# DressCode.net
KiCad netlist of a schematic drawn in EAGLE
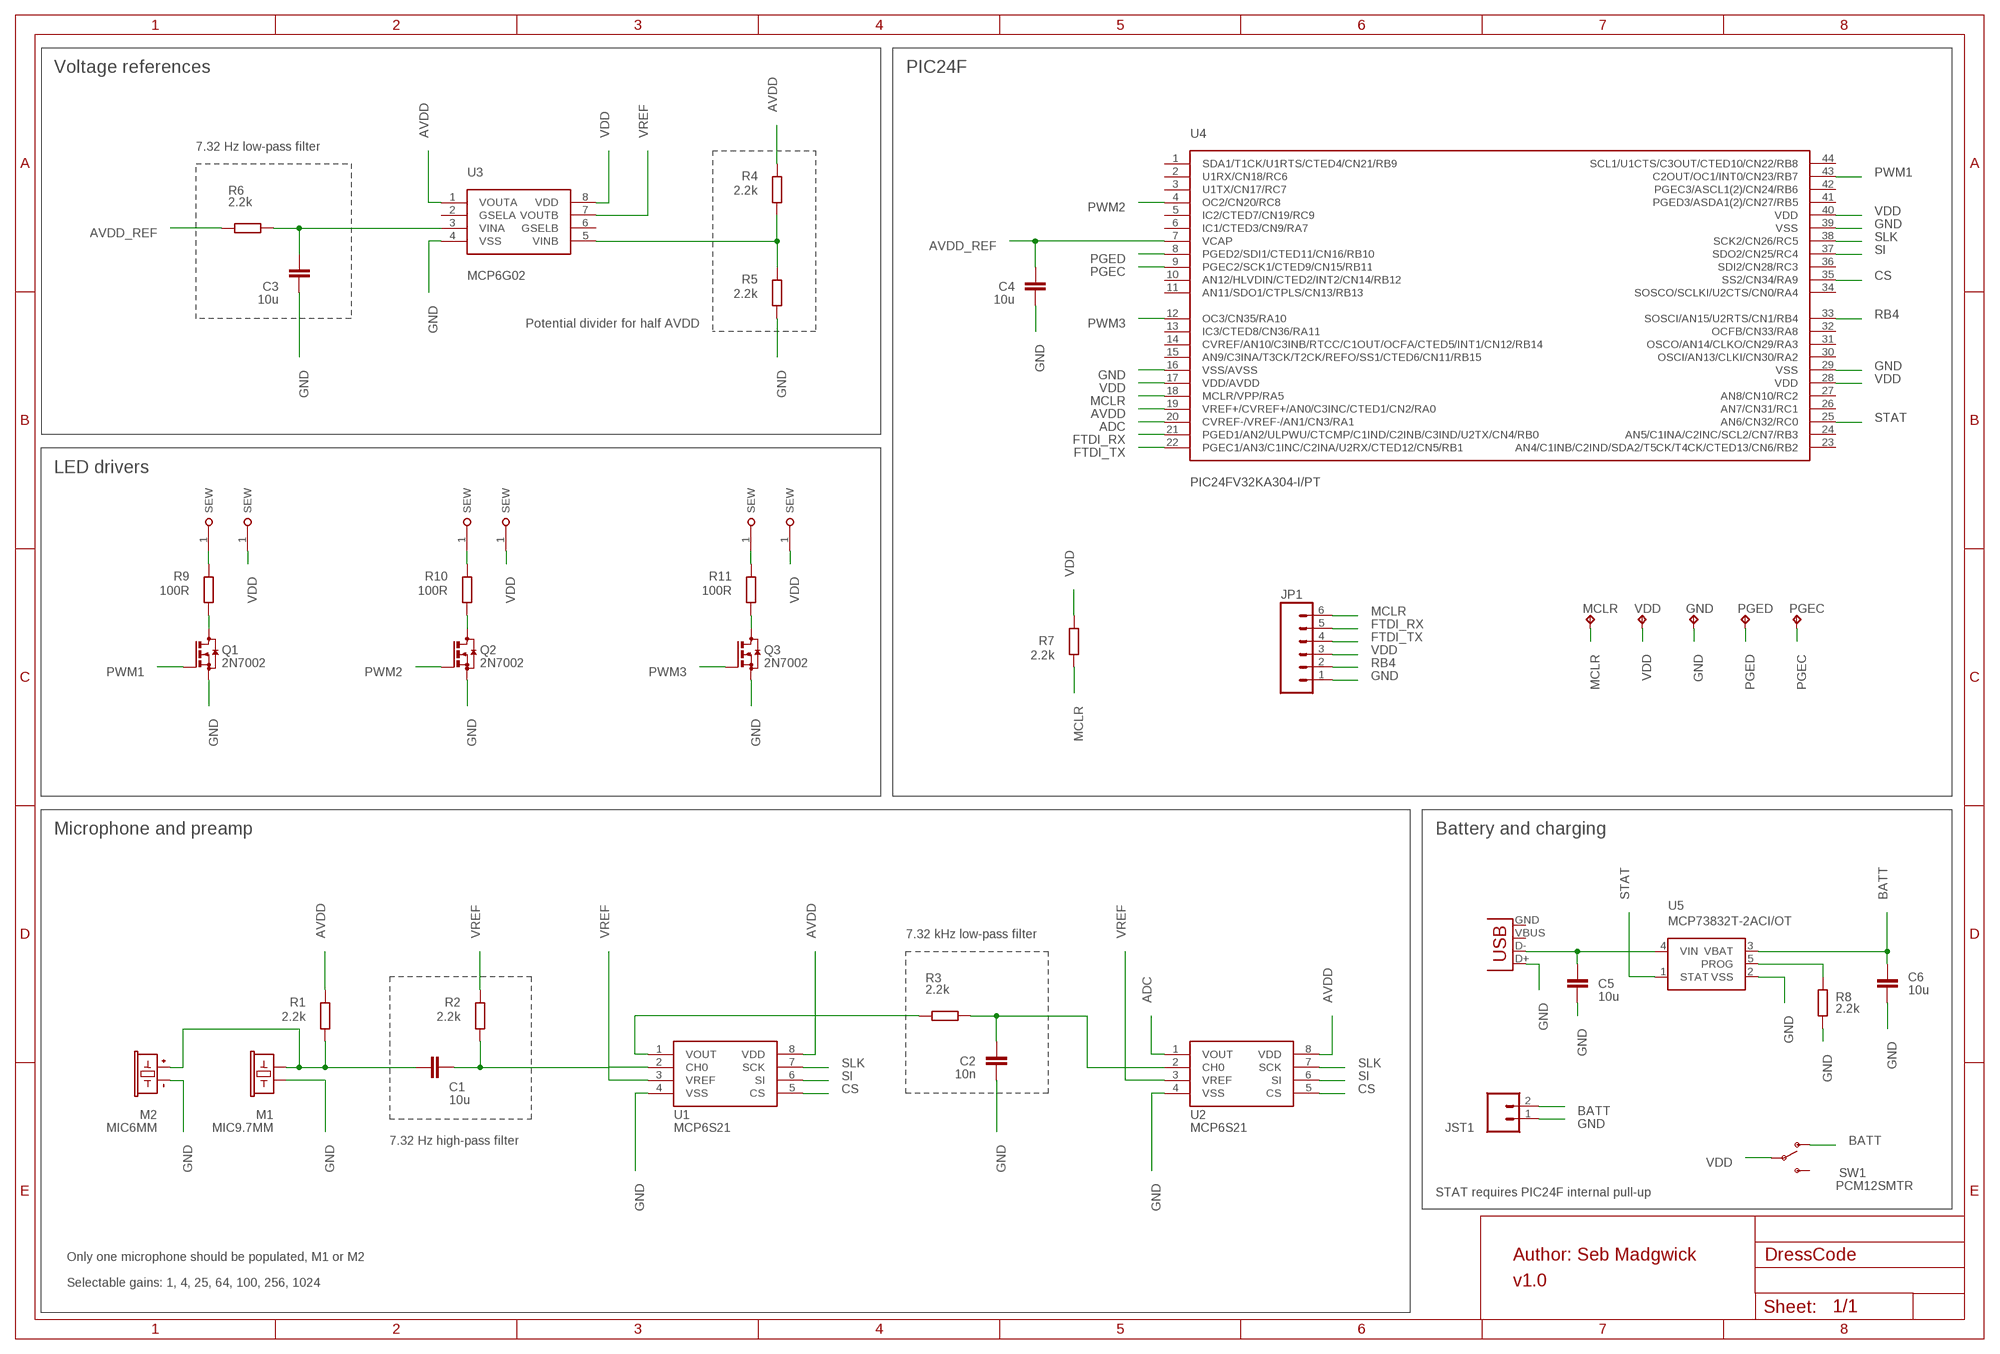
[diagram p0: schematic, sheet 1]

(export (version "E")
  (design (tool "Eeschema 10.0.6"))
  (components
    (comp (ref "C1")
      (value "10u")
      (footprint "eagle-import:C0805")
      (libsource (lib "eagle-import") (part "C-EUC0805"))
    )
    (comp (ref "C2")
      (value "10n")
      (footprint "eagle-import:C0805")
      (libsource (lib "eagle-import") (part "C-EUC0805"))
    )
    (comp (ref "C3")
      (value "10u")
      (footprint "eagle-import:C0805")
      (libsource (lib "eagle-import") (part "C-EUC0805"))
    )
    (comp (ref "C4")
      (value "10u")
      (footprint "eagle-import:C0805")
      (libsource (lib "eagle-import") (part "C-EUC0805"))
    )
    (comp (ref "C5")
      (value "10u")
      (footprint "eagle-import:C0805")
      (libsource (lib "eagle-import") (part "C-EUC0805"))
    )
    (comp (ref "C6")
      (value "10u")
      (footprint "eagle-import:C0805")
      (libsource (lib "eagle-import") (part "C-EUC0805"))
    )
    (comp (ref "GND")
      (value "TPTP16R")
      (footprint "eagle-import:TP16R")
      (libsource (lib "eagle-import") (part "TPTP16R"))
    )
    (comp (ref "JP1")
      (value "M06SIP")
      (footprint "eagle-import:1X06")
      (libsource (lib "eagle-import") (part "M06SIP"))
    )
    (comp (ref "JST1")
      (value "M02-JST-2MM-SMT")
      (footprint "eagle-import:JST-2-SMD")
      (libsource (lib "eagle-import") (part "M02-JST-2MM-SMT"))
    )
    (comp (ref "M1")
      (value "MIC9.7MM")
      (footprint "eagle-import:MIC-9.7MM")
      (libsource (lib "eagle-import") (part "MIC9.7MM"))
    )
    (comp (ref "M2")
      (value "MIC6MM")
      (footprint "eagle-import:MIC-SMD")
      (libsource (lib "eagle-import") (part "MIC6MM"))
    )
    (comp (ref "MCLR")
      (value "TPTP16R")
      (footprint "eagle-import:TP16R")
      (libsource (lib "eagle-import") (part "TPTP16R"))
    )
    (comp (ref "PGEC")
      (value "TPTP16R")
      (footprint "eagle-import:TP16R")
      (libsource (lib "eagle-import") (part "TPTP16R"))
    )
    (comp (ref "PGED")
      (value "TPTP16R")
      (footprint "eagle-import:TP16R")
      (libsource (lib "eagle-import") (part "TPTP16R"))
    )
    (comp (ref "Q1")
      (value "2N7002")
      (footprint "eagle-import:SOT23")
      (libsource (lib "eagle-import") (part "BSS123"))
    )
    (comp (ref "Q2")
      (value "2N7002")
      (footprint "eagle-import:SOT23")
      (libsource (lib "eagle-import") (part "BSS123"))
    )
    (comp (ref "Q3")
      (value "2N7002")
      (footprint "eagle-import:SOT23")
      (libsource (lib "eagle-import") (part "BSS123"))
    )
    (comp (ref "R1")
      (value "2.2k")
      (footprint "eagle-import:R0805")
      (libsource (lib "eagle-import") (part "R-EU_R0805"))
    )
    (comp (ref "R2")
      (value "2.2k")
      (footprint "eagle-import:R0805")
      (libsource (lib "eagle-import") (part "R-EU_R0805"))
    )
    (comp (ref "R3")
      (value "2.2k")
      (footprint "eagle-import:R0805")
      (libsource (lib "eagle-import") (part "R-EU_R0805"))
    )
    (comp (ref "R4")
      (value "2.2k")
      (footprint "eagle-import:R0805")
      (libsource (lib "eagle-import") (part "R-EU_R0805"))
    )
    (comp (ref "R5")
      (value "2.2k")
      (footprint "eagle-import:R0805")
      (libsource (lib "eagle-import") (part "R-EU_R0805"))
    )
    (comp (ref "R6")
      (value "2.2k")
      (footprint "eagle-import:R0805")
      (libsource (lib "eagle-import") (part "R-EU_R0805"))
    )
    (comp (ref "R7")
      (value "2.2k")
      (footprint "eagle-import:R0805")
      (libsource (lib "eagle-import") (part "R-EU_R0805"))
    )
    (comp (ref "R8")
      (value "2.2k")
      (footprint "eagle-import:R0805")
      (libsource (lib "eagle-import") (part "R-EU_R0805"))
    )
    (comp (ref "R9")
      (value "100R")
      (footprint "eagle-import:R0805")
      (libsource (lib "eagle-import") (part "R-EU_R0805"))
    )
    (comp (ref "R10")
      (value "100R")
      (footprint "eagle-import:R0805")
      (libsource (lib "eagle-import") (part "R-EU_R0805"))
    )
    (comp (ref "R11")
      (value "100R")
      (footprint "eagle-import:R0805")
      (libsource (lib "eagle-import") (part "R-EU_R0805"))
    )
    (comp (ref "SW1")
      (value "PCM12SMTR")
      (footprint "eagle-import:PCM12SMTR")
      (libsource (lib "eagle-import") (part "PCM12SMTR"))
    )
    (comp (ref "U$4")
      (value "DRESSCODE_SEW_PADC")
      (footprint "eagle-import:DRESSCODE_SEW_PAD_CIRC")
      (libsource (lib "eagle-import") (part "DRESSCODE_SEW_PADC"))
    )
    (comp (ref "U$5")
      (value "DRESSCODE_SEW_PADC")
      (footprint "eagle-import:DRESSCODE_SEW_PAD_CIRC")
      (libsource (lib "eagle-import") (part "DRESSCODE_SEW_PADC"))
    )
    (comp (ref "U$6")
      (value "DRESSCODE_SEW_PADC")
      (footprint "eagle-import:DRESSCODE_SEW_PAD_CIRC")
      (libsource (lib "eagle-import") (part "DRESSCODE_SEW_PADC"))
    )
    (comp (ref "U$7")
      (value "DRESSCODE_SEW_PADS")
      (footprint "eagle-import:DRESSCODE_SEW_PAD_SQR")
      (libsource (lib "eagle-import") (part "DRESSCODE_SEW_PADS"))
    )
    (comp (ref "U$8")
      (value "DRESSCODE_SEW_PADS")
      (footprint "eagle-import:DRESSCODE_SEW_PAD_SQR")
      (libsource (lib "eagle-import") (part "DRESSCODE_SEW_PADS"))
    )
    (comp (ref "U$10")
      (value "DRESSCODE_SEW_PADS")
      (footprint "eagle-import:DRESSCODE_SEW_PAD_SQR")
      (libsource (lib "eagle-import") (part "DRESSCODE_SEW_PADS"))
    )
    (comp (ref "U1")
      (value "MCP6S21")
      (footprint "eagle-import:SOIC-8")
      (libsource (lib "eagle-import") (part "MCP6S21"))
    )
    (comp (ref "U2")
      (value "MCP6S21")
      (footprint "eagle-import:SOIC-8")
      (libsource (lib "eagle-import") (part "MCP6S21"))
    )
    (comp (ref "U3")
      (value "MCP6G02")
      (footprint "eagle-import:SOIC-8")
      (libsource (lib "eagle-import") (part "MCP6G02"))
    )
    (comp (ref "U4")
      (value "PIC24FV32KA304-I/PT")
      (footprint "eagle-import:TQFP44")
      (libsource (lib "eagle-import") (part "PIC24FV32KA304-I/PT"))
    )
    (comp (ref "U5")
      (value "MCP73832T-2ACI/OT")
      (footprint "eagle-import:SOT23-5")
      (libsource (lib "eagle-import") (part "MCP73831"))
    )
    (comp (ref "USB1")
      (value "USB-MICROB")
      (footprint "eagle-import:USB-MICROB")
      (libsource (lib "eagle-import") (part "USB-MICROB"))
    )
    (comp (ref "VDD")
      (value "TPTP16R")
      (footprint "eagle-import:TP16R")
      (libsource (lib "eagle-import") (part "TPTP16R"))
    )
  )
  (nets
    (net (code "1") (name "/ADC") (class "Default")
      (node (ref "U2") (pin "1") (pinfunction "VOUT_1") (pintype "bidirectional"))
      (node (ref "U4") (pin "20") (pinfunction "CVREF-/VREF-/AN1/CN3/RA1_20") (pintype "bidirectional"))
    )
    (net (code "2") (name "/AVDD") (class "Default")
      (node (ref "R1") (pin "2") (pinfunction "2_2") (pintype "passive"))
      (node (ref "R4") (pin "2") (pinfunction "2_2") (pintype "passive"))
      (node (ref "U1") (pin "8") (pinfunction "VDD_8") (pintype "bidirectional"))
      (node (ref "U2") (pin "8") (pinfunction "VDD_8") (pintype "bidirectional"))
      (node (ref "U3") (pin "1") (pinfunction "VOUTA_1") (pintype "bidirectional"))
      (node (ref "U4") (pin "19") (pinfunction "VREF+/CVREF+/AN0/C3INC/CTED1/CN2/RA0_19") (pintype "bidirectional"))
    )
    (net (code "3") (name "/AVDD_REF") (class "Default")
      (node (ref "C4") (pin "2") (pinfunction "2_2") (pintype "passive"))
      (node (ref "R6") (pin "1") (pinfunction "1_1") (pintype "passive"))
      (node (ref "U4") (pin "7") (pinfunction "VCAP_7") (pintype "bidirectional"))
    )
    (net (code "4") (name "/BATT") (class "Default")
      (node (ref "C6") (pin "2") (pinfunction "2_2") (pintype "passive"))
      (node (ref "JST1") (pin "2") (pinfunction "2_2") (pintype "passive"))
      (node (ref "SW1") (pin "1") (pinfunction "O_1") (pintype "passive"))
      (node (ref "U5") (pin "3") (pinfunction "VBAT_3") (pintype "power_in"))
    )
    (net (code "5") (name "/CS") (class "Default")
      (node (ref "U1") (pin "5") (pinfunction "CS_5") (pintype "bidirectional"))
      (node (ref "U2") (pin "5") (pinfunction "CS_5") (pintype "bidirectional"))
      (node (ref "U4") (pin "35") (pinfunction "SS2/CN34/RA9_35") (pintype "bidirectional"))
    )
    (net (code "6") (name "/FTDI_RX") (class "Default")
      (node (ref "JP1") (pin "5") (pinfunction "5_5") (pintype "passive"))
      (node (ref "U4") (pin "21") (pinfunction "PGED1/AN2/ULPWU/CTCMP/C1IND/C2INB/C3IND/U2TX/CN4/RB0_21") (pintype "bidirectional"))
    )
    (net (code "7") (name "/FTDI_TX") (class "Default")
      (node (ref "JP1") (pin "4") (pinfunction "4_4") (pintype "passive"))
      (node (ref "U4") (pin "22") (pinfunction "PGEC1/AN3/C1INC/C2INA/U2RX/CTED12/CN5/RB1_22") (pintype "bidirectional"))
    )
    (net (code "8") (name "/GND") (class "Default")
      (node (ref "C2") (pin "2") (pinfunction "2_2") (pintype "passive"))
      (node (ref "C3") (pin "1") (pinfunction "1_1") (pintype "passive"))
      (node (ref "C4") (pin "1") (pinfunction "1_1") (pintype "passive"))
      (node (ref "C5") (pin "1") (pinfunction "1_1") (pintype "passive"))
      (node (ref "C6") (pin "1") (pinfunction "1_1") (pintype "passive"))
      (node (ref "GND") (pin "TP") (pinfunction "TP_TP") (pintype "input"))
      (node (ref "JP1") (pin "1") (pinfunction "1_1") (pintype "passive"))
      (node (ref "JST1") (pin "1") (pinfunction "1_1") (pintype "passive"))
      (node (ref "M1") (pin "2") (pinfunction "2_2") (pintype "passive"))
      (node (ref "M2") (pin "-") (pinfunction "-_-") (pintype "passive"))
      (node (ref "Q1") (pin "2") (pinfunction "S_2") (pintype "passive"))
      (node (ref "Q2") (pin "2") (pinfunction "S_2") (pintype "passive"))
      (node (ref "Q3") (pin "2") (pinfunction "S_2") (pintype "passive"))
      (node (ref "R5") (pin "1") (pinfunction "1_1") (pintype "passive"))
      (node (ref "R8") (pin "1") (pinfunction "1_1") (pintype "passive"))
      (node (ref "U1") (pin "4") (pinfunction "VSS_4") (pintype "bidirectional"))
      (node (ref "U2") (pin "4") (pinfunction "VSS_4") (pintype "bidirectional"))
      (node (ref "U3") (pin "4") (pinfunction "VSS_4") (pintype "bidirectional"))
      (node (ref "U4") (pin "16") (pinfunction "VSS/AVSS_16") (pintype "bidirectional"))
      (node (ref "U4") (pin "29") (pinfunction "VSS_29") (pintype "bidirectional"))
      (node (ref "U4") (pin "39") (pinfunction "VSS_39") (pintype "bidirectional"))
      (node (ref "U5") (pin "2") (pinfunction "VSS_2") (pintype "power_in"))
      (node (ref "USB1") (pin "D+") (pinfunction "D+_D+") (pintype "bidirectional"))
    )
    (net (code "9") (name "/MCLR") (class "Default")
      (node (ref "JP1") (pin "6") (pinfunction "6_6") (pintype "passive"))
      (node (ref "MCLR") (pin "TP") (pinfunction "TP_TP") (pintype "input"))
      (node (ref "R7") (pin "1") (pinfunction "1_1") (pintype "passive"))
      (node (ref "U4") (pin "18") (pinfunction "MCLR/VPP/RA5_18") (pintype "bidirectional"))
    )
    (net (code "10") (name "/PGEC") (class "Default")
      (node (ref "PGEC") (pin "TP") (pinfunction "TP_TP") (pintype "input"))
      (node (ref "U4") (pin "9") (pinfunction "PGEC2/SCK1/CTED9/CN15/RB11_9") (pintype "bidirectional"))
    )
    (net (code "11") (name "/PGED") (class "Default")
      (node (ref "PGED") (pin "TP") (pinfunction "TP_TP") (pintype "input"))
      (node (ref "U4") (pin "8") (pinfunction "PGED2/SDI1/CTED11/CN16/RB10_8") (pintype "bidirectional"))
    )
    (net (code "12") (name "/PWM1") (class "Default")
      (node (ref "Q1") (pin "1") (pinfunction "G_1") (pintype "passive"))
      (node (ref "U4") (pin "43") (pinfunction "C2OUT/OC1/INT0/CN23/RB7_43") (pintype "bidirectional"))
    )
    (net (code "13") (name "/PWM2") (class "Default")
      (node (ref "Q2") (pin "1") (pinfunction "G_1") (pintype "passive"))
      (node (ref "U4") (pin "4") (pinfunction "OC2/CN20/RC8_4") (pintype "bidirectional"))
    )
    (net (code "14") (name "/PWM3") (class "Default")
      (node (ref "Q3") (pin "1") (pinfunction "G_1") (pintype "passive"))
      (node (ref "U4") (pin "12") (pinfunction "OC3/CN35/RA10_12") (pintype "bidirectional"))
    )
    (net (code "15") (name "/RB4") (class "Default")
      (node (ref "JP1") (pin "2") (pinfunction "2_2") (pintype "passive"))
      (node (ref "U4") (pin "33") (pinfunction "SOSCI/AN15/U2RTS/CN1/RB4_33") (pintype "bidirectional"))
    )
    (net (code "16") (name "/SI") (class "Default")
      (node (ref "U1") (pin "6") (pinfunction "SI_6") (pintype "bidirectional"))
      (node (ref "U2") (pin "6") (pinfunction "SI_6") (pintype "bidirectional"))
      (node (ref "U4") (pin "37") (pinfunction "SDO2/CN25/RC4_37") (pintype "bidirectional"))
    )
    (net (code "17") (name "/SLK") (class "Default")
      (node (ref "U1") (pin "7") (pinfunction "SCK_7") (pintype "bidirectional"))
      (node (ref "U2") (pin "7") (pinfunction "SCK_7") (pintype "bidirectional"))
      (node (ref "U4") (pin "38") (pinfunction "SCK2/CN26/RC5_38") (pintype "bidirectional"))
    )
    (net (code "18") (name "/STAT") (class "Default")
      (node (ref "U4") (pin "25") (pinfunction "AN6/CN32/RC0_25") (pintype "bidirectional"))
      (node (ref "U5") (pin "1") (pinfunction "STAT_1") (pintype "output"))
    )
    (net (code "19") (name "/VDD") (class "Default")
      (node (ref "JP1") (pin "3") (pinfunction "3_3") (pintype "passive"))
      (node (ref "R7") (pin "2") (pinfunction "2_2") (pintype "passive"))
      (node (ref "SW1") (pin "2") (pinfunction "P_2") (pintype "passive"))
      (node (ref "U$4") (pin "1") (pinfunction "SEW_1") (pintype "bidirectional"))
      (node (ref "U$5") (pin "1") (pinfunction "SEW_1") (pintype "bidirectional"))
      (node (ref "U$6") (pin "1") (pinfunction "SEW_1") (pintype "bidirectional"))
      (node (ref "U3") (pin "8") (pinfunction "VDD_8") (pintype "bidirectional"))
      (node (ref "U4") (pin "17") (pinfunction "VDD/AVDD_17") (pintype "bidirectional"))
      (node (ref "U4") (pin "28") (pinfunction "VDD_28") (pintype "bidirectional"))
      (node (ref "U4") (pin "40") (pinfunction "VDD_40") (pintype "bidirectional"))
      (node (ref "VDD") (pin "TP") (pinfunction "TP_TP") (pintype "input"))
    )
    (net (code "20") (name "/VREF") (class "Default")
      (node (ref "R2") (pin "2") (pinfunction "2_2") (pintype "passive"))
      (node (ref "U1") (pin "3") (pinfunction "VREF_3") (pintype "bidirectional"))
      (node (ref "U2") (pin "3") (pinfunction "VREF_3") (pintype "bidirectional"))
      (node (ref "U3") (pin "7") (pinfunction "VOUTB_7") (pintype "bidirectional"))
    )
    (net (code "21") (name "Net-(C1-Pad1)") (class "Default")
      (node (ref "C1") (pin "1") (pinfunction "1_1") (pintype "passive"))
      (node (ref "M1") (pin "1") (pinfunction "1_1") (pintype "passive"))
      (node (ref "M2") (pin "+") (pinfunction "+_+") (pintype "passive"))
      (node (ref "R1") (pin "1") (pinfunction "1_1") (pintype "passive"))
    )
    (net (code "22") (name "Net-(Q1-D)") (class "Default")
      (node (ref "Q1") (pin "3") (pinfunction "D_3") (pintype "passive"))
      (node (ref "R9") (pin "1") (pinfunction "1_1") (pintype "passive"))
    )
    (net (code "23") (name "Net-(Q2-D)") (class "Default")
      (node (ref "Q2") (pin "3") (pinfunction "D_3") (pintype "passive"))
      (node (ref "R10") (pin "1") (pinfunction "1_1") (pintype "passive"))
    )
    (net (code "24") (name "Net-(Q3-D)") (class "Default")
      (node (ref "Q3") (pin "3") (pinfunction "D_3") (pintype "passive"))
      (node (ref "R11") (pin "1") (pinfunction "1_1") (pintype "passive"))
    )
    (net (code "25") (name "Net-(U$7-SEW)") (class "Default")
      (node (ref "R9") (pin "2") (pinfunction "2_2") (pintype "passive"))
      (node (ref "U$7") (pin "1") (pinfunction "SEW_1") (pintype "bidirectional"))
    )
    (net (code "26") (name "Net-(U$8-SEW)") (class "Default")
      (node (ref "R10") (pin "2") (pinfunction "2_2") (pintype "passive"))
      (node (ref "U$8") (pin "1") (pinfunction "SEW_1") (pintype "bidirectional"))
    )
    (net (code "27") (name "Net-(U$10-SEW)") (class "Default")
      (node (ref "R11") (pin "2") (pinfunction "2_2") (pintype "passive"))
      (node (ref "U$10") (pin "1") (pinfunction "SEW_1") (pintype "bidirectional"))
    )
    (net (code "28") (name "Net-(U1-CH0)") (class "Default")
      (node (ref "C1") (pin "2") (pinfunction "2_2") (pintype "passive"))
      (node (ref "R2") (pin "1") (pinfunction "1_1") (pintype "passive"))
      (node (ref "U1") (pin "2") (pinfunction "CH0_2") (pintype "bidirectional"))
    )
    (net (code "29") (name "Net-(U1-VOUT)") (class "Default")
      (node (ref "R3") (pin "1") (pinfunction "1_1") (pintype "passive"))
      (node (ref "U1") (pin "1") (pinfunction "VOUT_1") (pintype "bidirectional"))
    )
    (net (code "30") (name "Net-(U2-CH0)") (class "Default")
      (node (ref "C2") (pin "1") (pinfunction "1_1") (pintype "passive"))
      (node (ref "R3") (pin "2") (pinfunction "2_2") (pintype "passive"))
      (node (ref "U2") (pin "2") (pinfunction "CH0_2") (pintype "bidirectional"))
    )
    (net (code "31") (name "Net-(U3-VINA)") (class "Default")
      (node (ref "C3") (pin "2") (pinfunction "2_2") (pintype "passive"))
      (node (ref "R6") (pin "2") (pinfunction "2_2") (pintype "passive"))
      (node (ref "U3") (pin "3") (pinfunction "VINA_3") (pintype "bidirectional"))
    )
    (net (code "32") (name "Net-(U3-VINB)") (class "Default")
      (node (ref "R4") (pin "1") (pinfunction "1_1") (pintype "passive"))
      (node (ref "R5") (pin "2") (pinfunction "2_2") (pintype "passive"))
      (node (ref "U3") (pin "5") (pinfunction "VINB_5") (pintype "bidirectional"))
    )
    (net (code "33") (name "Net-(U5-PROG)") (class "Default")
      (node (ref "R8") (pin "2") (pinfunction "2_2") (pintype "passive"))
      (node (ref "U5") (pin "5") (pinfunction "PROG_5") (pintype "input"))
    )
    (net (code "34") (name "Net-(U5-VIN)") (class "Default")
      (node (ref "C5") (pin "2") (pinfunction "2_2") (pintype "passive"))
      (node (ref "U5") (pin "4") (pinfunction "VIN_4") (pintype "power_in"))
      (node (ref "USB1") (pin "D-") (pinfunction "D-_D-") (pintype "bidirectional"))
    )
    (net (code "35") (name "unconnected-(SW1-S-Pad3)") (class "Default")
      (node (ref "SW1") (pin "3") (pinfunction "S_3") (pintype "passive"))
    )
    (net (code "36") (name "unconnected-(U3-GSELA-Pad2)") (class "Default")
      (node (ref "U3") (pin "2") (pinfunction "GSELA_2") (pintype "bidirectional"))
    )
    (net (code "37") (name "unconnected-(U3-GSELB-Pad6)") (class "Default")
      (node (ref "U3") (pin "6") (pinfunction "GSELB_6") (pintype "bidirectional"))
    )
    (net (code "38") (name "unconnected-(U4-AN4{slash}C1INB{slash}C2IND{slash}SDA2{slash}T5CK{slash}T4CK{slash}CTED13{slash}CN6{slash}RB2-Pad23)") (class "Default")
      (node (ref "U4") (pin "23") (pinfunction "AN4/C1INB/C2IND/SDA2/T5CK/T4CK/CTED13/CN6/RB2_23") (pintype "bidirectional"))
    )
    (net (code "39") (name "unconnected-(U4-AN5{slash}C1INA{slash}C2INC{slash}SCL2{slash}CN7{slash}RB3-Pad24)") (class "Default")
      (node (ref "U4") (pin "24") (pinfunction "AN5/C1INA/C2INC/SCL2/CN7/RB3_24") (pintype "bidirectional"))
    )
    (net (code "40") (name "unconnected-(U4-AN7{slash}CN31{slash}RC1-Pad26)") (class "Default")
      (node (ref "U4") (pin "26") (pinfunction "AN7/CN31/RC1_26") (pintype "bidirectional"))
    )
    (net (code "41") (name "unconnected-(U4-AN8{slash}CN10{slash}RC2-Pad27)") (class "Default")
      (node (ref "U4") (pin "27") (pinfunction "AN8/CN10/RC2_27") (pintype "bidirectional"))
    )
    (net (code "42") (name "unconnected-(U4-AN9{slash}C3INA{slash}T3CK{slash}T2CK{slash}REFO{slash}SS1{slash}CTED6{slash}CN11{slash}RB15-Pad15)") (class "Default")
      (node (ref "U4") (pin "15") (pinfunction "AN9/C3INA/T3CK/T2CK/REFO/SS1/CTED6/CN11/RB15_15") (pintype "bidirectional"))
    )
    (net (code "43") (name "unconnected-(U4-AN11{slash}SDO1{slash}CTPLS{slash}CN13{slash}RB13-Pad11)") (class "Default")
      (node (ref "U4") (pin "11") (pinfunction "AN11/SDO1/CTPLS/CN13/RB13_11") (pintype "bidirectional"))
    )
    (net (code "44") (name "unconnected-(U4-AN12{slash}HLVDIN{slash}CTED2{slash}INT2{slash}CN14{slash}RB12-Pad10)") (class "Default")
      (node (ref "U4") (pin "10") (pinfunction "AN12/HLVDIN/CTED2/INT2/CN14/RB12_10") (pintype "bidirectional"))
    )
    (net (code "45") (name "unconnected-(U4-CVREF{slash}AN10{slash}C3INB{slash}RTCC{slash}C1OUT{slash}OCFA{slash}CTED5{slash}INT1{slash}CN12{slash}RB14-Pad14)") (class "Default")
      (node (ref "U4") (pin "14") (pinfunction "CVREF/AN10/C3INB/RTCC/C1OUT/OCFA/CTED5/INT1/CN12/RB14_14") (pintype "bidirectional"))
    )
    (net (code "46") (name "unconnected-(U4-IC1{slash}CTED3{slash}CN9{slash}RA7-Pad6)") (class "Default")
      (node (ref "U4") (pin "6") (pinfunction "IC1/CTED3/CN9/RA7_6") (pintype "bidirectional"))
    )
    (net (code "47") (name "unconnected-(U4-IC2{slash}CTED7{slash}CN19{slash}RC9-Pad5)") (class "Default")
      (node (ref "U4") (pin "5") (pinfunction "IC2/CTED7/CN19/RC9_5") (pintype "bidirectional"))
    )
    (net (code "48") (name "unconnected-(U4-IC3{slash}CTED8{slash}CN36{slash}RA11-Pad13)") (class "Default")
      (node (ref "U4") (pin "13") (pinfunction "IC3/CTED8/CN36/RA11_13") (pintype "bidirectional"))
    )
    (net (code "49") (name "unconnected-(U4-OCFB{slash}CN33{slash}RA8-Pad32)") (class "Default")
      (node (ref "U4") (pin "32") (pinfunction "OCFB/CN33/RA8_32") (pintype "bidirectional"))
    )
    (net (code "50") (name "unconnected-(U4-OSCI{slash}AN13{slash}CLKI{slash}CN30{slash}RA2-Pad30)") (class "Default")
      (node (ref "U4") (pin "30") (pinfunction "OSCI/AN13/CLKI/CN30/RA2_30") (pintype "bidirectional"))
    )
    (net (code "51") (name "unconnected-(U4-OSCO{slash}AN14{slash}CLKO{slash}CN29{slash}RA3-Pad31)") (class "Default")
      (node (ref "U4") (pin "31") (pinfunction "OSCO/AN14/CLKO/CN29/RA3_31") (pintype "bidirectional"))
    )
    (net (code "52") (name "unconnected-(U4-PGEC3{slash}ASCL1(2){slash}CN24{slash}RB6-Pad42)") (class "Default")
      (node (ref "U4") (pin "42") (pinfunction "PGEC3/ASCL1(2)/CN24/RB6_42") (pintype "bidirectional"))
    )
    (net (code "53") (name "unconnected-(U4-PGED3{slash}ASDA1(2){slash}CN27{slash}RB5-Pad41)") (class "Default")
      (node (ref "U4") (pin "41") (pinfunction "PGED3/ASDA1(2)/CN27/RB5_41") (pintype "bidirectional"))
    )
    (net (code "54") (name "unconnected-(U4-SCL1{slash}U1CTS{slash}C3OUT{slash}CTED10{slash}CN22{slash}RB8-Pad44)") (class "Default")
      (node (ref "U4") (pin "44") (pinfunction "SCL1/U1CTS/C3OUT/CTED10/CN22/RB8_44") (pintype "bidirectional"))
    )
    (net (code "55") (name "unconnected-(U4-SDA1{slash}T1CK{slash}U1RTS{slash}CTED4{slash}CN21{slash}RB9-Pad1)") (class "Default")
      (node (ref "U4") (pin "1") (pinfunction "SDA1/T1CK/U1RTS/CTED4/CN21/RB9_1") (pintype "bidirectional"))
    )
    (net (code "56") (name "unconnected-(U4-SDI2{slash}CN28{slash}RC3-Pad36)") (class "Default")
      (node (ref "U4") (pin "36") (pinfunction "SDI2/CN28/RC3_36") (pintype "bidirectional"))
    )
    (net (code "57") (name "unconnected-(U4-SOSCO{slash}SCLKI{slash}U2CTS{slash}CN0{slash}RA4-Pad34)") (class "Default")
      (node (ref "U4") (pin "34") (pinfunction "SOSCO/SCLKI/U2CTS/CN0/RA4_34") (pintype "bidirectional"))
    )
    (net (code "58") (name "unconnected-(U4-U1RX{slash}CN18{slash}RC6-Pad2)") (class "Default")
      (node (ref "U4") (pin "2") (pinfunction "U1RX/CN18/RC6_2") (pintype "bidirectional"))
    )
    (net (code "59") (name "unconnected-(U4-U1TX{slash}CN17{slash}RC7-Pad3)") (class "Default")
      (node (ref "U4") (pin "3") (pinfunction "U1TX/CN17/RC7_3") (pintype "bidirectional"))
    )
    (net (code "60") (name "unconnected-(USB1-PadGND)") (class "Default")
      (node (ref "USB1") (pin "GND") (pinfunction "GND_GND") (pintype "bidirectional"))
    )
    (net (code "61") (name "unconnected-(USB1-PadVBUS)") (class "Default")
      (node (ref "USB1") (pin "VBUS") (pinfunction "VBUS_VBUS") (pintype "bidirectional"))
    )
  )
)
